# PCB-SLIDER-S.net
KiCad netlist of a schematic drawn in EAGLE
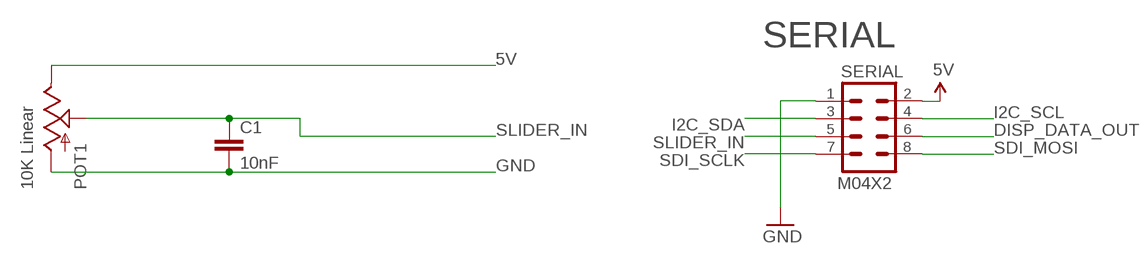
[diagram p0: schematic, sheet 1]

(export (version "E")
  (design (tool "Eeschema 10.0.6"))
  (components
    (comp (ref "C1")
      (value "10nF")
      (footprint "eagle-import:0603-CAP")
      (libsource (lib "eagle-import") (part "CAP0603-CAP"))
    )
    (comp (ref "POT1")
      (value "10K Linear")
      (footprint "eagle-import:SLIDER60")
      (libsource (lib "eagle-import") (part "SLIDER60"))
    )
    (comp (ref "SERIAL")
      (value "M04X2")
      (footprint "eagle-import:2X4")
      (libsource (lib "eagle-import") (part "M04X2"))
    )
  )
  (nets
    (net (code "1") (name "/DISP_DATA_OUT") (class "Default")
      (node (ref "SERIAL") (pin "6") (pinfunction "6_6") (pintype "passive"))
    )
    (net (code "2") (name "/I2C_SCL") (class "Default")
      (node (ref "SERIAL") (pin "4") (pinfunction "4_4") (pintype "passive"))
    )
    (net (code "3") (name "/I2C_SDA") (class "Default")
      (node (ref "SERIAL") (pin "3") (pinfunction "3_3") (pintype "passive"))
    )
    (net (code "4") (name "/SDI_MOSI") (class "Default")
      (node (ref "SERIAL") (pin "8") (pinfunction "8_8") (pintype "passive"))
    )
    (net (code "5") (name "/SDI_SCLK") (class "Default")
      (node (ref "SERIAL") (pin "7") (pinfunction "7_7") (pintype "passive"))
    )
    (net (code "6") (name "/SLIDER_IN") (class "Default")
      (node (ref "C1") (pin "1") (pinfunction "1_1") (pintype "passive"))
      (node (ref "POT1") (pin "2A") (pinfunction "S_2A") (pintype "passive"))
      (node (ref "SERIAL") (pin "5") (pinfunction "5_5") (pintype "passive"))
    )
    (net (code "7") (name "5V") (class "Default")
      (node (ref "POT1") (pin "1") (pinfunction "E_1") (pintype "passive"))
      (node (ref "SERIAL") (pin "2") (pinfunction "2_2") (pintype "passive"))
    )
    (net (code "8") (name "GND") (class "Default")
      (node (ref "C1") (pin "2") (pinfunction "2_2") (pintype "passive"))
      (node (ref "POT1") (pin "3") (pinfunction "A_3") (pintype "passive"))
      (node (ref "SERIAL") (pin "1") (pinfunction "1_1") (pintype "passive"))
    )
  )
)
